# Sheet2.net
KiCad netlist of a schematic drawn in Altium Designer
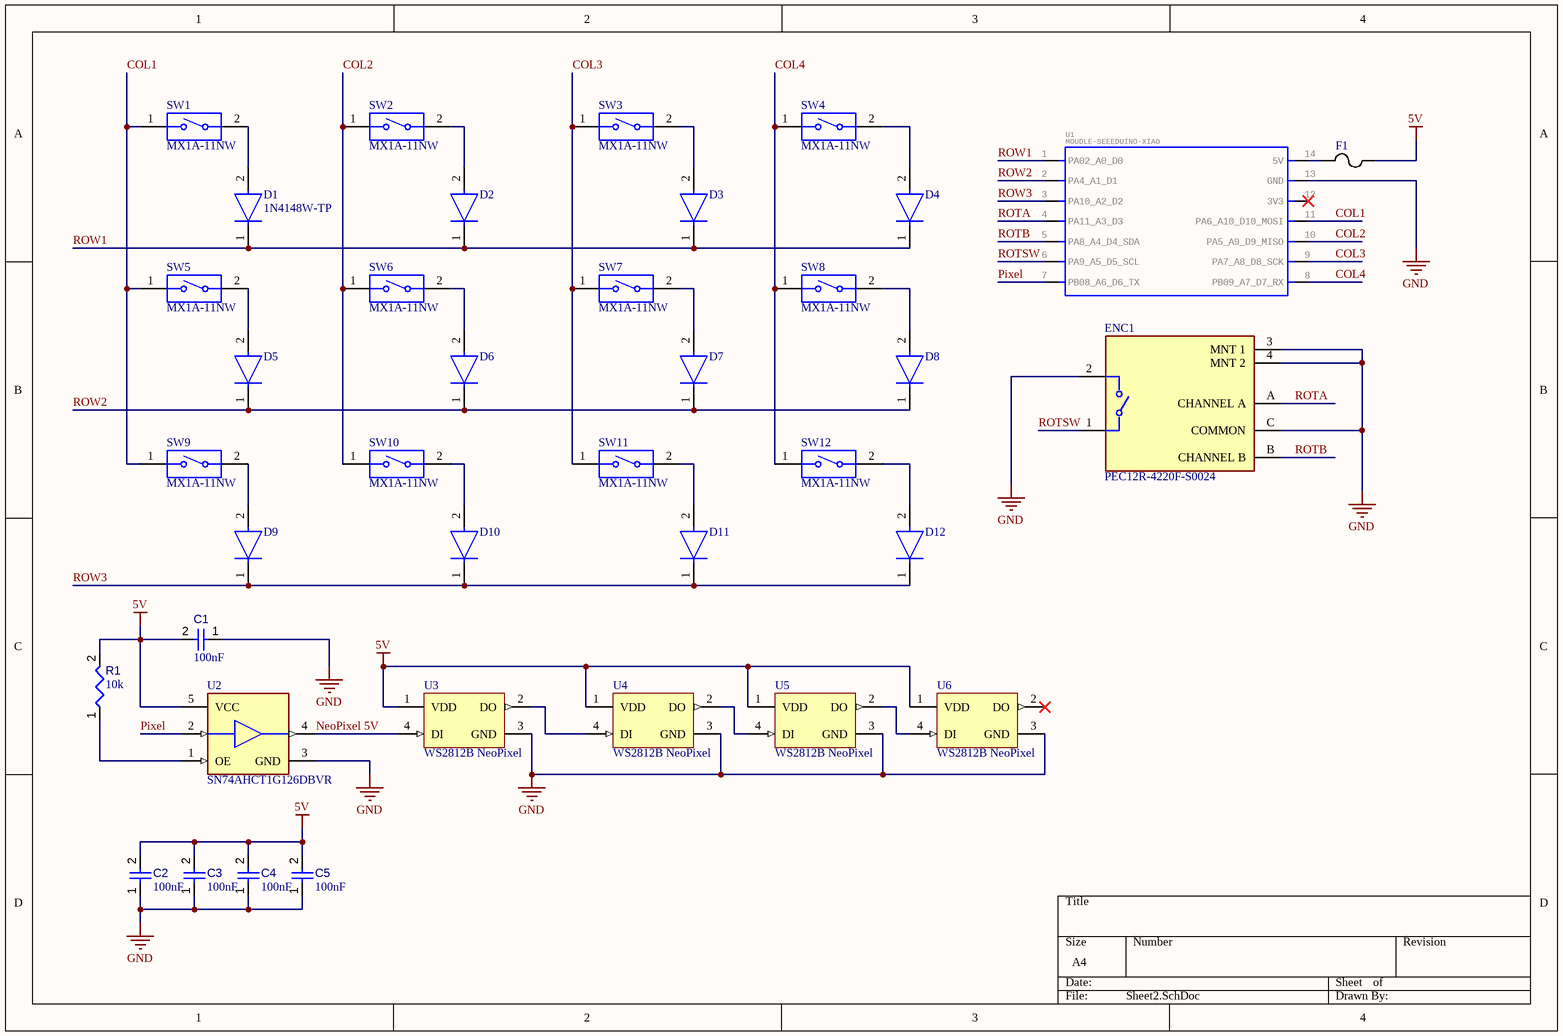
[diagram p0: Sheet2.SchDoc]

(export (version "E")
  (design (tool "Eeschema 10.0.6"))
  (components
    (comp (ref "C1")
      (value "100nF")
      (footprint "CAPC1608X90X40NL10T20")
      (description "Chip Capacitor, 100 nF, +/- 10%, 50 V, 0603 (1608 Metric)")
      (fields (field (name "TOLERANCE") "10%") (field (name "Comment") "Capacitor 100 nF +/-10% 50 V 0603"))
      (libsource (lib "Joel Lee") (part "CAP-NP-2"))
    )
    (comp (ref "C2")
      (value "100nF")
      (footprint "CAPC1608X90X40NL10T20")
      (description "Chip Capacitor, 100 nF, +/- 10%, 50 V, 0603 (1608 Metric)")
      (fields (field (name "TOLERANCE") "10%") (field (name "Comment") "Capacitor 100 nF +/-10% 50 V 0603"))
      (libsource (lib "Joel Lee") (part "CAP-NP-2"))
    )
    (comp (ref "C3")
      (value "100nF")
      (footprint "CAPC1608X90X40NL10T20")
      (description "Chip Capacitor, 100 nF, +/- 10%, 50 V, 0603 (1608 Metric)")
      (fields (field (name "TOLERANCE") "10%") (field (name "Comment") "Capacitor 100 nF +/-10% 50 V 0603"))
      (libsource (lib "Joel Lee") (part "CAP-NP-2"))
    )
    (comp (ref "C4")
      (value "100nF")
      (footprint "CAPC1608X90X40NL10T20")
      (description "Chip Capacitor, 100 nF, +/- 10%, 50 V, 0603 (1608 Metric)")
      (fields (field (name "TOLERANCE") "10%") (field (name "Comment") "Capacitor 100 nF +/-10% 50 V 0603"))
      (libsource (lib "Joel Lee") (part "CAP-NP-2"))
    )
    (comp (ref "C5")
      (value "100nF")
      (footprint "CAPC1608X90X40NL10T20")
      (description "Chip Capacitor, 100 nF, +/- 10%, 50 V, 0603 (1608 Metric)")
      (fields (field (name "TOLERANCE") "10%") (field (name "Comment") "Capacitor 100 nF +/-10% 50 V 0603"))
      (libsource (lib "Joel Lee") (part "CAP-NP-2"))
    )
    (comp (ref "D1")
      (value "1N4148W-TP")
      (footprint "FP-SOD-123-IPC_A")
      (description "DIODE GEN PURP 100V 150MA SOD123")
      (libsource (lib "Altium Content Vault") (part "d7152d700b627762746794eb795d46e"))
    )
    (comp (ref "D2")
      (value "1N4148W-TP")
      (footprint "FP-SOD-123-IPC_A")
      (description "DIODE GEN PURP 100V 150MA SOD123")
      (libsource (lib "Altium Content Vault") (part "d7152d700b627762746794eb795d46e"))
    )
    (comp (ref "D3")
      (value "1N4148W-TP")
      (footprint "FP-SOD-123-IPC_A")
      (description "DIODE GEN PURP 100V 150MA SOD123")
      (libsource (lib "Altium Content Vault") (part "d7152d700b627762746794eb795d46e"))
    )
    (comp (ref "D4")
      (value "1N4148W-TP")
      (footprint "FP-SOD-123-IPC_A")
      (description "DIODE GEN PURP 100V 150MA SOD123")
      (libsource (lib "Altium Content Vault") (part "d7152d700b627762746794eb795d46e"))
    )
    (comp (ref "D5")
      (value "1N4148W-TP")
      (footprint "FP-SOD-123-IPC_A")
      (description "DIODE GEN PURP 100V 150MA SOD123")
      (libsource (lib "Altium Content Vault") (part "d7152d700b627762746794eb795d46e"))
    )
    (comp (ref "D6")
      (value "1N4148W-TP")
      (footprint "FP-SOD-123-IPC_A")
      (description "DIODE GEN PURP 100V 150MA SOD123")
      (libsource (lib "Altium Content Vault") (part "d7152d700b627762746794eb795d46e"))
    )
    (comp (ref "D7")
      (value "1N4148W-TP")
      (footprint "FP-SOD-123-IPC_A")
      (description "DIODE GEN PURP 100V 150MA SOD123")
      (libsource (lib "Altium Content Vault") (part "d7152d700b627762746794eb795d46e"))
    )
    (comp (ref "D8")
      (value "1N4148W-TP")
      (footprint "FP-SOD-123-IPC_A")
      (description "DIODE GEN PURP 100V 150MA SOD123")
      (libsource (lib "Altium Content Vault") (part "d7152d700b627762746794eb795d46e"))
    )
    (comp (ref "D9")
      (value "1N4148W-TP")
      (footprint "FP-SOD-123-IPC_A")
      (description "DIODE GEN PURP 100V 150MA SOD123")
      (libsource (lib "Altium Content Vault") (part "d7152d700b627762746794eb795d46e"))
    )
    (comp (ref "D10")
      (value "1N4148W-TP")
      (footprint "FP-SOD-123-IPC_A")
      (description "DIODE GEN PURP 100V 150MA SOD123")
      (libsource (lib "Altium Content Vault") (part "d7152d700b627762746794eb795d46e"))
    )
    (comp (ref "D11")
      (value "1N4148W-TP")
      (footprint "FP-SOD-123-IPC_A")
      (description "DIODE GEN PURP 100V 150MA SOD123")
      (libsource (lib "Altium Content Vault") (part "d7152d700b627762746794eb795d46e"))
    )
    (comp (ref "D12")
      (value "1N4148W-TP")
      (footprint "FP-SOD-123-IPC_A")
      (description "DIODE GEN PURP 100V 150MA SOD123")
      (libsource (lib "Altium Content Vault") (part "d7152d700b627762746794eb795d46e"))
    )
    (comp (ref "ENC1")
      (value "PEC12R-4220F-S0024")
      (footprint "FP-PEC12R-4220F-S0024-MFG")
      (description "ROTARY ENCODER MECHANICAL 24PPR")
      (libsource (lib "Altium Content Vault") (part "94c173c7df275f4241826ab5d869309"))
    )
    (comp (ref "F1")
      (value "0ZCK0050FF2E")
      (footprint "0ZCK0050FF2E:0ZCK_BEL")
      (description "No Description Available")
      (libsource (lib "0ZCK0050FF2E") (part "0ZCK0050FF2E"))
    )
    (comp (ref "R1")
      (value "10k")
      (footprint "RESC2013X50X35ML15T15")
      (description "Chip Resistor, 10 KOhm, +/- 1%, 125 mW, -55 to 155 degC, 0805 (2012 Metric)")
      (fields (field (name "TOLERANCE") "1%") (field (name "POWER") "125mW"))
      (libsource (lib "Joel Lee") (part "RES-2"))
    )
    (comp (ref "SW1")
      (value "MX1A-11NW")
      (footprint "CHRY-MX1A-11NW_V")
      (libsource (lib "Joel Lee") (part "KEYSW-SPST-2"))
    )
    (comp (ref "SW2")
      (value "MX1A-11NW")
      (footprint "CHRY-MX1A-11NW_V")
      (libsource (lib "Joel Lee") (part "KEYSW-SPST-2"))
    )
    (comp (ref "SW3")
      (value "MX1A-11NW")
      (footprint "CHRY-MX1A-11NW_V")
      (libsource (lib "Joel Lee") (part "KEYSW-SPST-2"))
    )
    (comp (ref "SW4")
      (value "MX1A-11NW")
      (footprint "CHRY-MX1A-11NW_V")
      (libsource (lib "Joel Lee") (part "KEYSW-SPST-2"))
    )
    (comp (ref "SW5")
      (value "MX1A-11NW")
      (footprint "CHRY-MX1A-11NW_V")
      (libsource (lib "Joel Lee") (part "KEYSW-SPST-2"))
    )
    (comp (ref "SW6")
      (value "MX1A-11NW")
      (footprint "CHRY-MX1A-11NW_V")
      (libsource (lib "Joel Lee") (part "KEYSW-SPST-2"))
    )
    (comp (ref "SW7")
      (value "MX1A-11NW")
      (footprint "CHRY-MX1A-11NW_V")
      (libsource (lib "Joel Lee") (part "KEYSW-SPST-2"))
    )
    (comp (ref "SW8")
      (value "MX1A-11NW")
      (footprint "CHRY-MX1A-11NW_V")
      (libsource (lib "Joel Lee") (part "KEYSW-SPST-2"))
    )
    (comp (ref "SW9")
      (value "MX1A-11NW")
      (footprint "CHRY-MX1A-11NW_V")
      (libsource (lib "Joel Lee") (part "KEYSW-SPST-2"))
    )
    (comp (ref "SW10")
      (value "MX1A-11NW")
      (footprint "CHRY-MX1A-11NW_V")
      (libsource (lib "Joel Lee") (part "KEYSW-SPST-2"))
    )
    (comp (ref "SW11")
      (value "MX1A-11NW")
      (footprint "CHRY-MX1A-11NW_V")
      (libsource (lib "Joel Lee") (part "KEYSW-SPST-2"))
    )
    (comp (ref "SW12")
      (value "MX1A-11NW")
      (footprint "CHRY-MX1A-11NW_V")
      (libsource (lib "Joel Lee") (part "KEYSW-SPST-2"))
    )
    (comp (ref "U1")
      (value "MOUDLE-SEEEDUINO-XIAO")
      (footprint "MOUDLE14P-2-54-21X17-8MM")
      (fields (field (name "LIBRARYNAME") "Seeeduino-XIAO-footprint-eagle"))
      (libsource (lib "Seeeduino-XIAO-footprint-eagle") (part "MOUDLE-SEEEDUINO-XIAO"))
    )
    (comp (ref "U2")
      (value "SN74AHCT1G126DBVR")
      (footprint "FP-DBV0005A-IPC_C")
      (description "IC BUF NON-INVERT 5.5V SOT23-5")
      (libsource (lib "Altium Content Vault") (part "6270cd932aa2b03682f8fb9cbffdd68"))
    )
    (comp (ref "U3")
      (value "WS2812B NeoPixel")
      (footprint "ADA-RGB-1655_V")
      (description "WS2812B 5050 RGB LED WITH INTEGRATED DRIVER CHIP PACK OF 10")
      (libsource (lib "Joel Lee") (part "ADA-RGB-1655-4"))
    )
    (comp (ref "U4")
      (value "WS2812B NeoPixel")
      (footprint "ADA-RGB-1655_V")
      (description "WS2812B 5050 RGB LED WITH INTEGRATED DRIVER CHIP PACK OF 10")
      (libsource (lib "Joel Lee") (part "ADA-RGB-1655-4"))
    )
    (comp (ref "U5")
      (value "WS2812B NeoPixel")
      (footprint "ADA-RGB-1655_V")
      (description "WS2812B 5050 RGB LED WITH INTEGRATED DRIVER CHIP PACK OF 10")
      (libsource (lib "Joel Lee") (part "ADA-RGB-1655-4"))
    )
    (comp (ref "U6")
      (value "WS2812B NeoPixel")
      (footprint "ADA-RGB-1655_V")
      (description "WS2812B 5050 RGB LED WITH INTEGRATED DRIVER CHIP PACK OF 10")
      (libsource (lib "Joel Lee") (part "ADA-RGB-1655-4"))
    )
  )
  (nets
    (net (code "1") (name "/COL1") (class "Default")
      (node (ref "SW1") (pin "1") (pinfunction "1_1") (pintype "passive"))
      (node (ref "SW5") (pin "1") (pinfunction "1_1") (pintype "passive"))
      (node (ref "SW9") (pin "1") (pinfunction "1_1") (pintype "passive"))
      (node (ref "U1") (pin "11") (pinfunction "PA6_A10_D10_MOSI_11") (pintype "bidirectional"))
    )
    (net (code "2") (name "/COL2") (class "Default")
      (node (ref "SW10") (pin "1") (pinfunction "1_1") (pintype "passive"))
      (node (ref "SW2") (pin "1") (pinfunction "1_1") (pintype "passive"))
      (node (ref "SW6") (pin "1") (pinfunction "1_1") (pintype "passive"))
      (node (ref "U1") (pin "10") (pinfunction "PA5_A9_D9_MISO_10") (pintype "bidirectional"))
    )
    (net (code "3") (name "/COL3") (class "Default")
      (node (ref "SW11") (pin "1") (pinfunction "1_1") (pintype "passive"))
      (node (ref "SW3") (pin "1") (pinfunction "1_1") (pintype "passive"))
      (node (ref "SW7") (pin "1") (pinfunction "1_1") (pintype "passive"))
      (node (ref "U1") (pin "9") (pinfunction "PA7_A8_D8_SCK_9") (pintype "bidirectional"))
    )
    (net (code "4") (name "/COL4") (class "Default")
      (node (ref "SW12") (pin "1") (pinfunction "1_1") (pintype "passive"))
      (node (ref "SW4") (pin "1") (pinfunction "1_1") (pintype "passive"))
      (node (ref "SW8") (pin "1") (pinfunction "1_1") (pintype "passive"))
      (node (ref "U1") (pin "8") (pinfunction "PB09_A7_D7_RX_8") (pintype "bidirectional"))
    )
    (net (code "5") (name "/NeoPixel 5V") (class "Default")
      (node (ref "U2") (pin "4") (pinfunction "Y_4") (pintype "output"))
      (node (ref "U3") (pin "4") (pinfunction "DI_4") (pintype "input"))
    )
    (net (code "6") (name "/Pixel") (class "Default")
      (node (ref "U1") (pin "7") (pinfunction "PB08_A6_D6_TX_7") (pintype "bidirectional"))
      (node (ref "U2") (pin "2") (pinfunction "A_2") (pintype "input"))
    )
    (net (code "7") (name "/ROTA") (class "Default")
      (node (ref "ENC1") (pin "A") (pinfunction "CHANNEL_A_A") (pintype "passive"))
      (node (ref "U1") (pin "4") (pinfunction "PA11_A3_D3_4") (pintype "bidirectional"))
    )
    (net (code "8") (name "/ROTB") (class "Default")
      (node (ref "ENC1") (pin "B") (pinfunction "CHANNEL_B_B") (pintype "passive"))
      (node (ref "U1") (pin "5") (pinfunction "PA8_A4_D4_SDA_5") (pintype "bidirectional"))
    )
    (net (code "9") (name "/ROTSW") (class "Default")
      (node (ref "ENC1") (pin "1") (pinfunction "1_1") (pintype "passive"))
      (node (ref "U1") (pin "6") (pinfunction "PA9_A5_D5_SCL_6") (pintype "bidirectional"))
    )
    (net (code "10") (name "/ROW1") (class "Default")
      (node (ref "D1") (pin "1") (pinfunction "C_1") (pintype "passive"))
      (node (ref "D2") (pin "1") (pinfunction "C_1") (pintype "passive"))
      (node (ref "D3") (pin "1") (pinfunction "C_1") (pintype "passive"))
      (node (ref "D4") (pin "1") (pinfunction "C_1") (pintype "passive"))
      (node (ref "U1") (pin "1") (pinfunction "PA02_A0_D0_1") (pintype "bidirectional"))
    )
    (net (code "11") (name "/ROW2") (class "Default")
      (node (ref "D5") (pin "1") (pinfunction "C_1") (pintype "passive"))
      (node (ref "D6") (pin "1") (pinfunction "C_1") (pintype "passive"))
      (node (ref "D7") (pin "1") (pinfunction "C_1") (pintype "passive"))
      (node (ref "D8") (pin "1") (pinfunction "C_1") (pintype "passive"))
      (node (ref "U1") (pin "2") (pinfunction "PA4_A1_D1_2") (pintype "bidirectional"))
    )
    (net (code "12") (name "/ROW3") (class "Default")
      (node (ref "D10") (pin "1") (pinfunction "C_1") (pintype "passive"))
      (node (ref "D11") (pin "1") (pinfunction "C_1") (pintype "passive"))
      (node (ref "D12") (pin "1") (pinfunction "C_1") (pintype "passive"))
      (node (ref "D9") (pin "1") (pinfunction "C_1") (pintype "passive"))
      (node (ref "U1") (pin "3") (pinfunction "PA10_A2_D2_3") (pintype "bidirectional"))
    )
    (net (code "13") (name "5V") (class "Default")
      (node (ref "C1") (pin "2") (pinfunction "2_2") (pintype "passive"))
      (node (ref "C2") (pin "2") (pinfunction "2_2") (pintype "passive"))
      (node (ref "C3") (pin "2") (pinfunction "2_2") (pintype "passive"))
      (node (ref "C4") (pin "2") (pinfunction "2_2") (pintype "passive"))
      (node (ref "C5") (pin "2") (pinfunction "2_2") (pintype "passive"))
      (node (ref "F1") (pin "2") (pinfunction "2_2") (pintype "passive"))
      (node (ref "R1") (pin "2") (pinfunction "2_2") (pintype "passive"))
      (node (ref "U2") (pin "5") (pinfunction "VCC_5") (pintype "power_in"))
      (node (ref "U3") (pin "1") (pinfunction "VDD_1") (pintype "power_in"))
      (node (ref "U4") (pin "1") (pinfunction "VDD_1") (pintype "power_in"))
      (node (ref "U5") (pin "1") (pinfunction "VDD_1") (pintype "power_in"))
      (node (ref "U6") (pin "1") (pinfunction "VDD_1") (pintype "power_in"))
    )
    (net (code "14") (name "GND") (class "Default")
      (node (ref "C1") (pin "1") (pinfunction "1_1") (pintype "passive"))
      (node (ref "C2") (pin "1") (pinfunction "1_1") (pintype "passive"))
      (node (ref "C3") (pin "1") (pinfunction "1_1") (pintype "passive"))
      (node (ref "C4") (pin "1") (pinfunction "1_1") (pintype "passive"))
      (node (ref "C5") (pin "1") (pinfunction "1_1") (pintype "passive"))
      (node (ref "ENC1") (pin "2") (pinfunction "2_2") (pintype "passive"))
      (node (ref "ENC1") (pin "3") (pinfunction "MNT_1_3") (pintype "passive"))
      (node (ref "ENC1") (pin "4") (pinfunction "MNT_2_4") (pintype "passive"))
      (node (ref "ENC1") (pin "C") (pinfunction "COMMON_C") (pintype "passive"))
      (node (ref "U1") (pin "13") (pinfunction "GND_13") (pintype "bidirectional"))
      (node (ref "U2") (pin "3") (pinfunction "GND_3") (pintype "power_in"))
      (node (ref "U3") (pin "3") (pinfunction "GND_3") (pintype "power_in"))
      (node (ref "U4") (pin "3") (pinfunction "GND_3") (pintype "power_in"))
      (node (ref "U5") (pin "3") (pinfunction "GND_3") (pintype "power_in"))
      (node (ref "U6") (pin "3") (pinfunction "GND_3") (pintype "power_in"))
    )
    (net (code "15") (name "Net-(D1-A)") (class "Default")
      (node (ref "D1") (pin "2") (pinfunction "A_2") (pintype "passive"))
      (node (ref "SW1") (pin "2") (pinfunction "2_2") (pintype "passive"))
    )
    (net (code "16") (name "Net-(D2-A)") (class "Default")
      (node (ref "D2") (pin "2") (pinfunction "A_2") (pintype "passive"))
      (node (ref "SW2") (pin "2") (pinfunction "2_2") (pintype "passive"))
    )
    (net (code "17") (name "Net-(D3-A)") (class "Default")
      (node (ref "D3") (pin "2") (pinfunction "A_2") (pintype "passive"))
      (node (ref "SW3") (pin "2") (pinfunction "2_2") (pintype "passive"))
    )
    (net (code "18") (name "Net-(D4-A)") (class "Default")
      (node (ref "D4") (pin "2") (pinfunction "A_2") (pintype "passive"))
      (node (ref "SW4") (pin "2") (pinfunction "2_2") (pintype "passive"))
    )
    (net (code "19") (name "Net-(D5-A)") (class "Default")
      (node (ref "D5") (pin "2") (pinfunction "A_2") (pintype "passive"))
      (node (ref "SW5") (pin "2") (pinfunction "2_2") (pintype "passive"))
    )
    (net (code "20") (name "Net-(D6-A)") (class "Default")
      (node (ref "D6") (pin "2") (pinfunction "A_2") (pintype "passive"))
      (node (ref "SW6") (pin "2") (pinfunction "2_2") (pintype "passive"))
    )
    (net (code "21") (name "Net-(D7-A)") (class "Default")
      (node (ref "D7") (pin "2") (pinfunction "A_2") (pintype "passive"))
      (node (ref "SW7") (pin "2") (pinfunction "2_2") (pintype "passive"))
    )
    (net (code "22") (name "Net-(D8-A)") (class "Default")
      (node (ref "D8") (pin "2") (pinfunction "A_2") (pintype "passive"))
      (node (ref "SW8") (pin "2") (pinfunction "2_2") (pintype "passive"))
    )
    (net (code "23") (name "Net-(D9-A)") (class "Default")
      (node (ref "D9") (pin "2") (pinfunction "A_2") (pintype "passive"))
      (node (ref "SW9") (pin "2") (pinfunction "2_2") (pintype "passive"))
    )
    (net (code "24") (name "Net-(D10-A)") (class "Default")
      (node (ref "D10") (pin "2") (pinfunction "A_2") (pintype "passive"))
      (node (ref "SW10") (pin "2") (pinfunction "2_2") (pintype "passive"))
    )
    (net (code "25") (name "Net-(D11-A)") (class "Default")
      (node (ref "D11") (pin "2") (pinfunction "A_2") (pintype "passive"))
      (node (ref "SW11") (pin "2") (pinfunction "2_2") (pintype "passive"))
    )
    (net (code "26") (name "Net-(D12-A)") (class "Default")
      (node (ref "D12") (pin "2") (pinfunction "A_2") (pintype "passive"))
      (node (ref "SW12") (pin "2") (pinfunction "2_2") (pintype "passive"))
    )
    (net (code "27") (name "Net-(U1-5V)") (class "Default")
      (node (ref "F1") (pin "1") (pinfunction "1_1") (pintype "passive"))
      (node (ref "U1") (pin "14") (pinfunction "5V_14") (pintype "bidirectional"))
    )
    (net (code "28") (name "Net-(U2-OE)") (class "Default")
      (node (ref "R1") (pin "1") (pinfunction "1_1") (pintype "passive"))
      (node (ref "U2") (pin "1") (pinfunction "OE_1") (pintype "input"))
    )
    (net (code "29") (name "Net-(U3-DO)") (class "Default")
      (node (ref "U3") (pin "2") (pinfunction "DO_2") (pintype "output"))
      (node (ref "U4") (pin "4") (pinfunction "DI_4") (pintype "input"))
    )
    (net (code "30") (name "Net-(U4-DO)") (class "Default")
      (node (ref "U4") (pin "2") (pinfunction "DO_2") (pintype "output"))
      (node (ref "U5") (pin "4") (pinfunction "DI_4") (pintype "input"))
    )
    (net (code "31") (name "Net-(U5-DO)") (class "Default")
      (node (ref "U5") (pin "2") (pinfunction "DO_2") (pintype "output"))
      (node (ref "U6") (pin "4") (pinfunction "DI_4") (pintype "input"))
    )
    (net (code "32") (name "unconnected-(U1-3V3-Pad12)") (class "Default")
      (node (ref "U1") (pin "12") (pinfunction "3V3_12") (pintype "bidirectional+no_connect"))
    )
    (net (code "33") (name "unconnected-(U6-DO-Pad2)") (class "Default")
      (node (ref "U6") (pin "2") (pinfunction "DO_2") (pintype "output+no_connect"))
    )
  )
)
